# iot_scheme.net
KiCad netlist of a schematic drawn in EAGLE
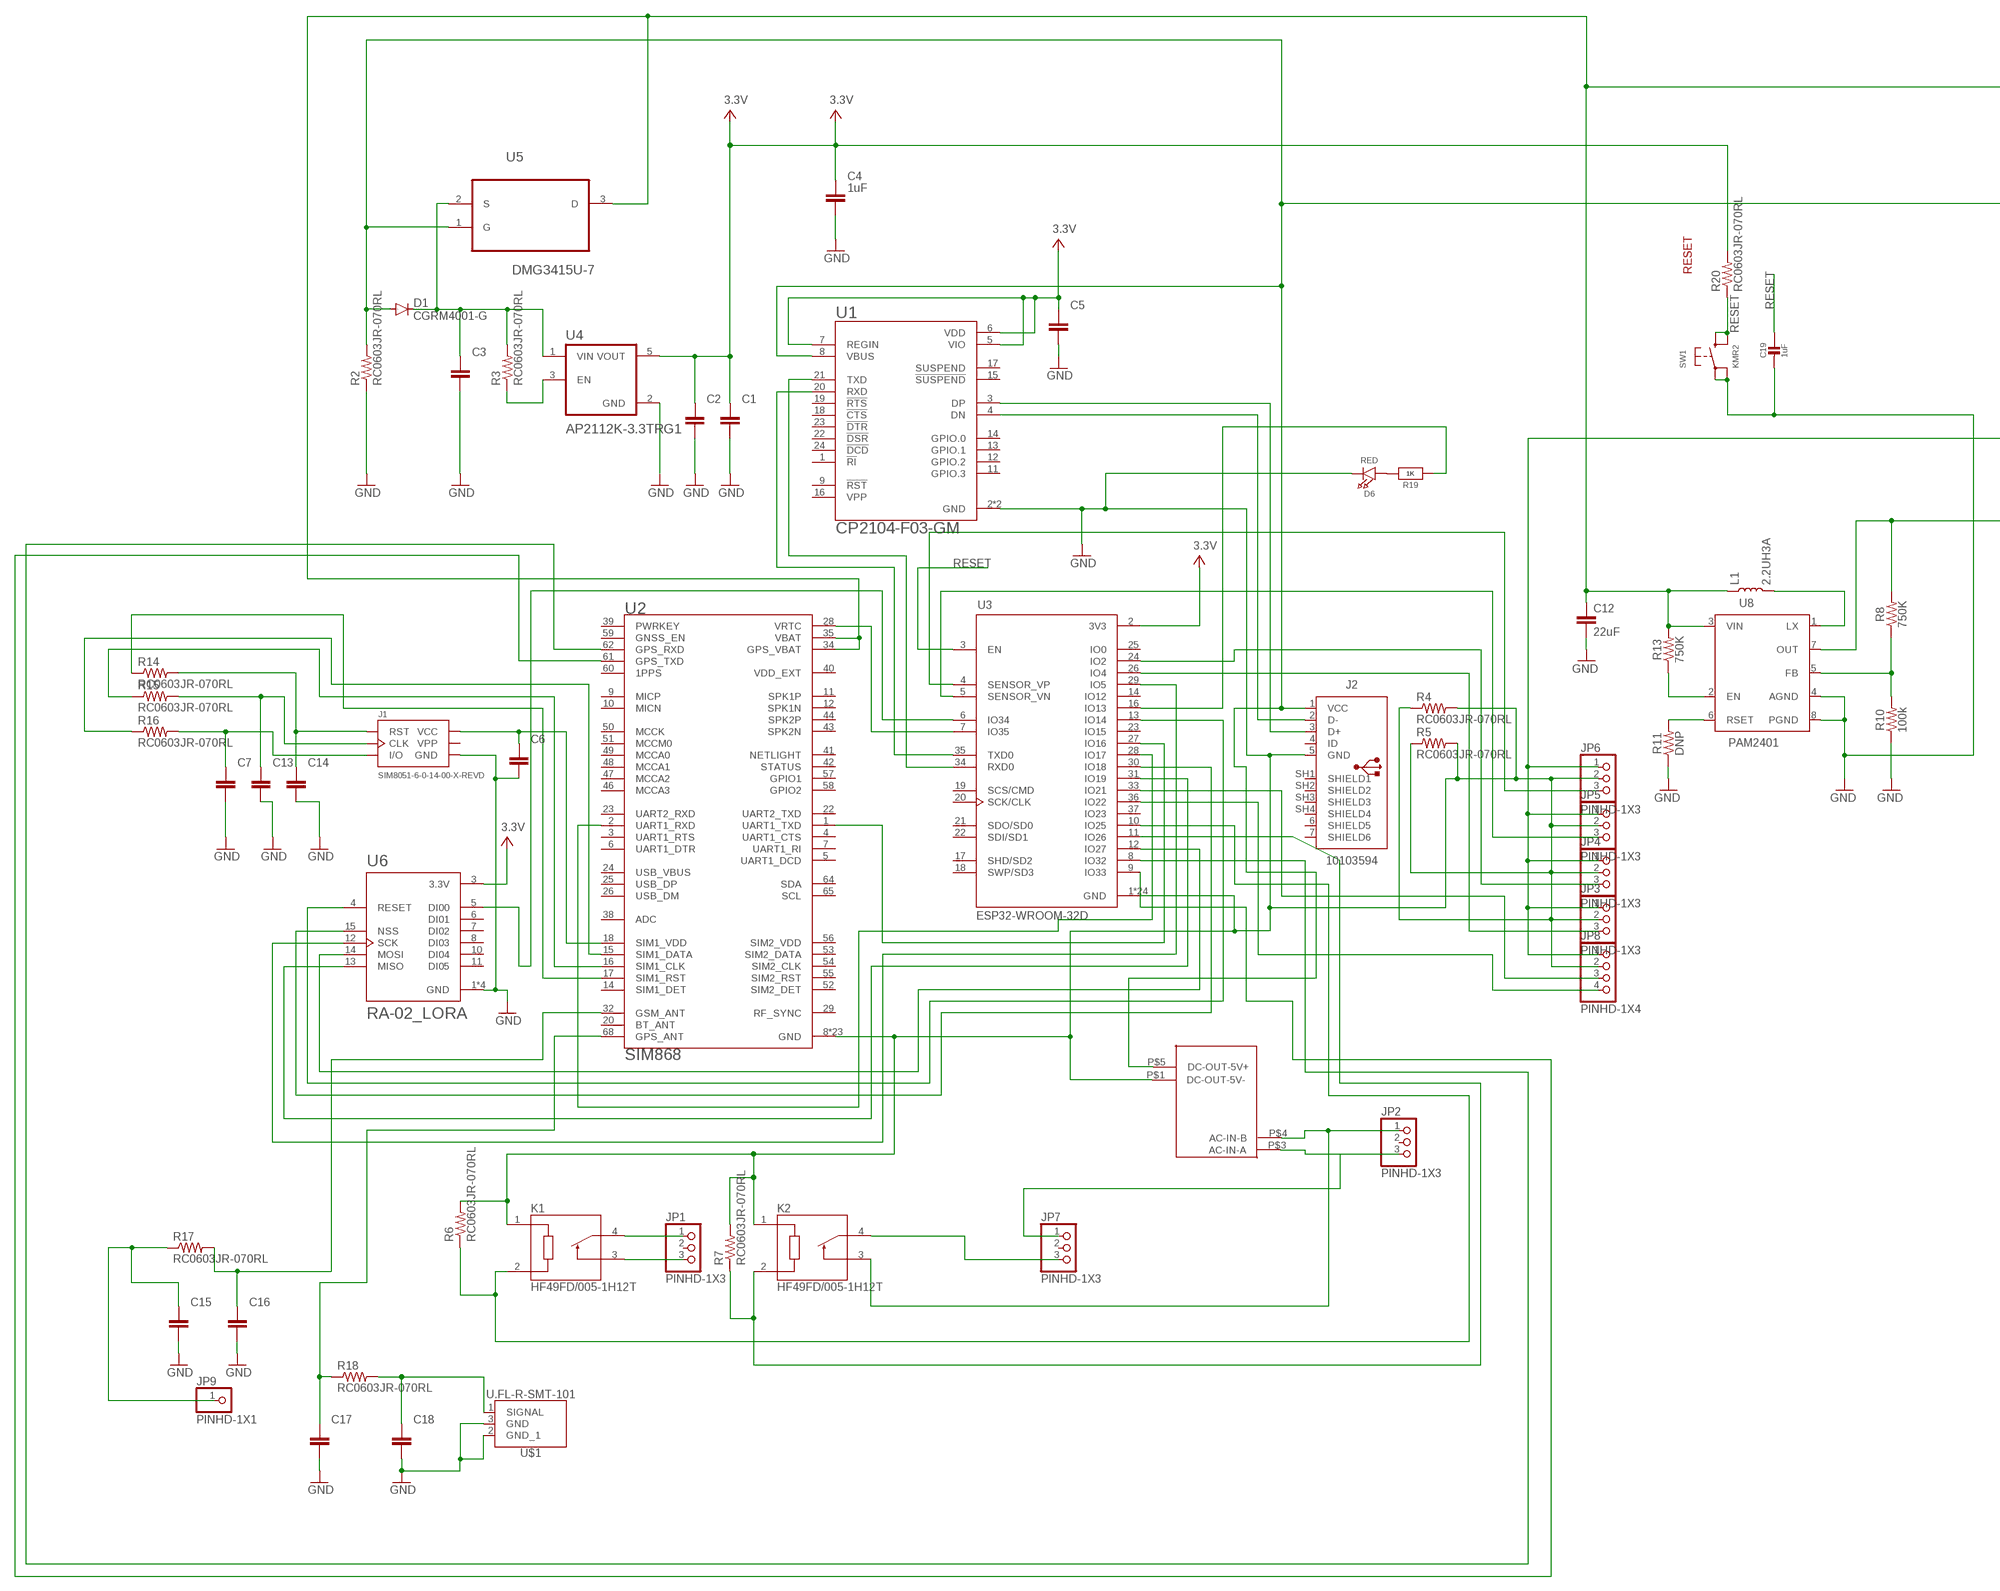
[diagram p0: schematic, sheet 1, part 1 of 2]
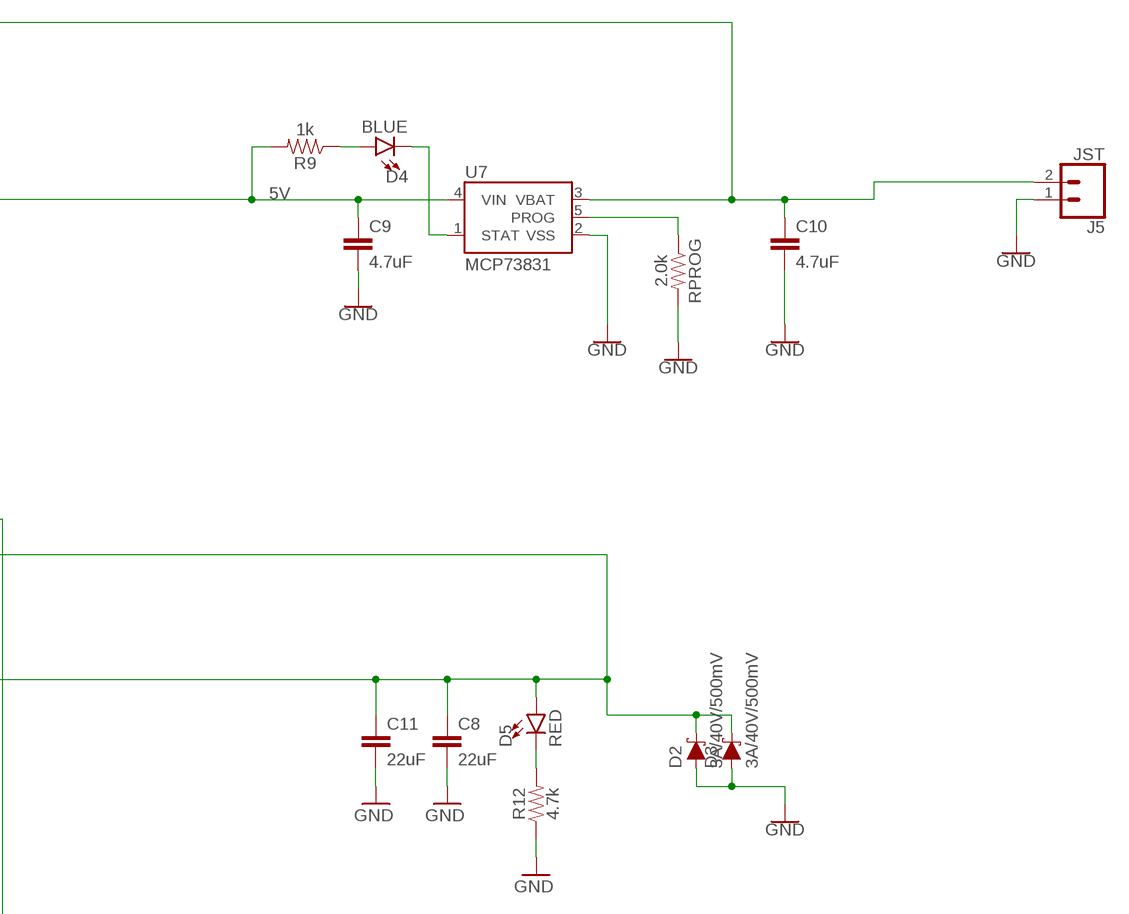
[diagram p1: schematic, sheet 1, part 2 of 2]

(export (version "E")
  (design (tool "Eeschema 10.0.6"))
  (components
    (comp (ref "C1")
      (value "C_CHIP-0603(1608-METRIC)")
      (footprint "eagle-import:CAPC1608X85")
      (libsource (lib "eagle-import") (part "CCHIP-0603(1608-METRIC)_"))
    )
    (comp (ref "C2")
      (value "C_CHIP-0603(1608-METRIC)")
      (footprint "eagle-import:CAPC1608X85")
      (libsource (lib "eagle-import") (part "CCHIP-0603(1608-METRIC)_"))
    )
    (comp (ref "C3")
      (value "C_CHIP-0603(1608-METRIC)")
      (footprint "eagle-import:CAPC1608X85")
      (libsource (lib "eagle-import") (part "CCHIP-0603(1608-METRIC)_"))
    )
    (comp (ref "C4")
      (value "1uF")
      (footprint "eagle-import:CAPC1608X85")
      (libsource (lib "eagle-import") (part "CCHIP-0603(1608-METRIC)_"))
    )
    (comp (ref "C5")
      (value "C_CHIP-0603(1608-METRIC)")
      (footprint "eagle-import:CAPC1608X85")
      (libsource (lib "eagle-import") (part "CCHIP-0603(1608-METRIC)_"))
    )
    (comp (ref "C6")
      (value "C_CHIP-0603(1608-METRIC)")
      (footprint "eagle-import:CAPC1608X85")
      (libsource (lib "eagle-import") (part "CCHIP-0603(1608-METRIC)_"))
    )
    (comp (ref "C7")
      (value "C_CHIP-0603(1608-METRIC)")
      (footprint "eagle-import:CAPC1608X85")
      (libsource (lib "eagle-import") (part "CCHIP-0603(1608-METRIC)_"))
    )
    (comp (ref "C8")
      (value "22uF")
      (footprint "eagle-import:0805")
      (libsource (lib "eagle-import") (part "22UF-0805-6.3V-20%"))
    )
    (comp (ref "C9")
      (value "4.7uF")
      (footprint "eagle-import:0603")
      (libsource (lib "eagle-import") (part "4.7UF0603"))
    )
    (comp (ref "C10")
      (value "4.7uF")
      (footprint "eagle-import:0603")
      (libsource (lib "eagle-import") (part "4.7UF0603"))
    )
    (comp (ref "C11")
      (value "22uF")
      (footprint "eagle-import:0805")
      (libsource (lib "eagle-import") (part "22UF-0805-6.3V-20%"))
    )
    (comp (ref "C12")
      (value "22uF")
      (footprint "eagle-import:0805")
      (libsource (lib "eagle-import") (part "22UF-0805-6.3V-20%"))
    )
    (comp (ref "C13")
      (value "C_CHIP-0603(1608-METRIC)")
      (footprint "eagle-import:CAPC1608X85")
      (libsource (lib "eagle-import") (part "CCHIP-0603(1608-METRIC)_"))
    )
    (comp (ref "C14")
      (value "C_CHIP-0603(1608-METRIC)")
      (footprint "eagle-import:CAPC1608X85")
      (libsource (lib "eagle-import") (part "CCHIP-0603(1608-METRIC)_"))
    )
    (comp (ref "C15")
      (value "C_CHIP-0603(1608-METRIC)")
      (footprint "eagle-import:CAPC1608X85")
      (libsource (lib "eagle-import") (part "CCHIP-0603(1608-METRIC)_"))
    )
    (comp (ref "C16")
      (value "C_CHIP-0603(1608-METRIC)")
      (footprint "eagle-import:CAPC1608X85")
      (libsource (lib "eagle-import") (part "CCHIP-0603(1608-METRIC)_"))
    )
    (comp (ref "C17")
      (value "C_CHIP-0603(1608-METRIC)")
      (footprint "eagle-import:CAPC1608X85")
      (libsource (lib "eagle-import") (part "CCHIP-0603(1608-METRIC)_"))
    )
    (comp (ref "C18")
      (value "C_CHIP-0603(1608-METRIC)")
      (footprint "eagle-import:CAPC1608X85")
      (libsource (lib "eagle-import") (part "CCHIP-0603(1608-METRIC)_"))
    )
    (comp (ref "C19")
      (value "1uF")
      (footprint "eagle-import:0603-NO")
      (libsource (lib "eagle-import") (part "CAP_CERAMIC0603_NO"))
    )
    (comp (ref "D1")
      (value "CGRM4001-G")
      (footprint "eagle-import:SOD-123_MINI-SMA")
      (libsource (lib "eagle-import") (part "CGRM400-G1"))
    )
    (comp (ref "D2")
      (value "3A/40V/500mV")
      (footprint "eagle-import:SMA-DIODE")
      (libsource (lib "eagle-import") (part "DIODE-SCHOTTKY-B340A"))
    )
    (comp (ref "D3")
      (value "3A/40V/500mV")
      (footprint "eagle-import:SMA-DIODE")
      (libsource (lib "eagle-import") (part "DIODE-SCHOTTKY-B340A"))
    )
    (comp (ref "D4")
      (value "BLUE")
      (footprint "eagle-import:LED-0603")
      (libsource (lib "eagle-import") (part "LED-BLUE0603"))
    )
    (comp (ref "D5")
      (value "RED")
      (footprint "eagle-import:LED-0603")
      (libsource (lib "eagle-import") (part "LED-RED0603"))
    )
    (comp (ref "D6")
      (value "RED")
      (footprint "eagle-import:CHIPLED_0805_NOOUTLINE")
      (libsource (lib "eagle-import") (part "LED0805_NOOUTLINE"))
    )
    (comp (ref "J1")
      (value "SIM8051-6-0-14-00-X-REVD")
      (footprint "eagle-import:GCT_SIM8051-6-0-14-00-X-REVD")
      (fields (field (name "MF") "Global Connector Technology") (field (name "MP") "SIM8051-6-0-14-00-A"))
      (libsource (lib "eagle-import") (part "SIM8051-6-0-14-00-X-REVD"))
    )
    (comp (ref "J2")
      (value "10103594")
      (footprint "eagle-import:10103594")
      (fields (field (name "MANUFACTURER") "Amphenol ICC (FCI)") (field (name "MPN") "10103594-0001LF"))
      (libsource (lib "eagle-import") (part "10103594"))
    )
    (comp (ref "J5")
      (value "JST")
      (footprint "eagle-import:JST-2-SMD")
      (libsource (lib "eagle-import") (part "CONN_02-JST-2MM-SMT"))
    )
    (comp (ref "JP1")
      (value "PINHD-1X3")
      (footprint "eagle-import:1X03")
      (libsource (lib "eagle-import") (part "PINHD-1X3"))
    )
    (comp (ref "JP2")
      (value "PINHD-1X3")
      (footprint "eagle-import:1X03")
      (libsource (lib "eagle-import") (part "PINHD-1X3"))
    )
    (comp (ref "JP3")
      (value "PINHD-1X3")
      (footprint "eagle-import:1X03")
      (libsource (lib "eagle-import") (part "PINHD-1X3"))
    )
    (comp (ref "JP4")
      (value "PINHD-1X3")
      (footprint "eagle-import:1X03")
      (libsource (lib "eagle-import") (part "PINHD-1X3"))
    )
    (comp (ref "JP5")
      (value "PINHD-1X3")
      (footprint "eagle-import:1X03")
      (libsource (lib "eagle-import") (part "PINHD-1X3"))
    )
    (comp (ref "JP6")
      (value "PINHD-1X3")
      (footprint "eagle-import:1X03")
      (libsource (lib "eagle-import") (part "PINHD-1X3"))
    )
    (comp (ref "JP7")
      (value "PINHD-1X3")
      (footprint "eagle-import:1X03")
      (libsource (lib "eagle-import") (part "PINHD-1X3"))
    )
    (comp (ref "JP8")
      (value "PINHD-1X4")
      (footprint "eagle-import:1X04")
      (libsource (lib "eagle-import") (part "PINHD-1X4"))
    )
    (comp (ref "JP9")
      (value "PINHD-1X1")
      (footprint "eagle-import:1X01")
      (libsource (lib "eagle-import") (part "PINHD-1X1"))
    )
    (comp (ref "K1")
      (value "HF49FD/005-1H12T")
      (footprint "eagle-import:RELAY_HF49FD_005-1H12T")
      (fields (field (name "MF") "Hongfa"))
      (libsource (lib "eagle-import") (part "HF49FD/005-1H12T"))
    )
    (comp (ref "K2")
      (value "HF49FD/005-1H12T")
      (footprint "eagle-import:RELAY_HF49FD_005-1H12T")
      (fields (field (name "MF") "Hongfa"))
      (libsource (lib "eagle-import") (part "HF49FD/005-1H12T"))
    )
    (comp (ref "L1")
      (value "2.2UH3A")
      (footprint "eagle-import:INDUCTOR_4X4MM")
      (libsource (lib "eagle-import") (part "INDUCTOR-IFSC1515AHER2R2M01"))
    )
    (comp (ref "R1")
      (value "AC-DC-5V")
      (footprint "eagle-import:MYFOOT")
      (libsource (lib "eagle-import") (part "AC-DC-5V"))
    )
    (comp (ref "R2")
      (value "RC0603JR-070RL")
      (footprint "eagle-import:RES_0603")
      (fields
        (field (name "DIGIKEY_PART_NUMBER") "311-0.0GRTR-ND")
        (field (name "MANUFACTURER") "Yageo")
        (field (name "CREATED_BY") "PCBLayout.com")
      )
      (libsource (lib "eagle-import") (part "RC0603JR-070RL"))
    )
    (comp (ref "R3")
      (value "RC0603JR-070RL")
      (footprint "eagle-import:RES_0603")
      (fields
        (field (name "DIGIKEY_PART_NUMBER") "311-0.0GRTR-ND")
        (field (name "MANUFACTURER") "Yageo")
        (field (name "CREATED_BY") "PCBLayout.com")
      )
      (libsource (lib "eagle-import") (part "RC0603JR-070RL"))
    )
    (comp (ref "R4")
      (value "RC0603JR-070RL")
      (footprint "eagle-import:RES_0603")
      (fields
        (field (name "DIGIKEY_PART_NUMBER") "311-0.0GRTR-ND")
        (field (name "MANUFACTURER") "Yageo")
        (field (name "CREATED_BY") "PCBLayout.com")
      )
      (libsource (lib "eagle-import") (part "RC0603JR-070RL"))
    )
    (comp (ref "R5")
      (value "RC0603JR-070RL")
      (footprint "eagle-import:RES_0603")
      (fields
        (field (name "DIGIKEY_PART_NUMBER") "311-0.0GRTR-ND")
        (field (name "MANUFACTURER") "Yageo")
        (field (name "CREATED_BY") "PCBLayout.com")
      )
      (libsource (lib "eagle-import") (part "RC0603JR-070RL"))
    )
    (comp (ref "R6")
      (value "RC0603JR-070RL")
      (footprint "eagle-import:RES_0603")
      (fields
        (field (name "DIGIKEY_PART_NUMBER") "311-0.0GRTR-ND")
        (field (name "MANUFACTURER") "Yageo")
        (field (name "CREATED_BY") "PCBLayout.com")
      )
      (libsource (lib "eagle-import") (part "RC0603JR-070RL"))
    )
    (comp (ref "R7")
      (value "RC0603JR-070RL")
      (footprint "eagle-import:RES_0603")
      (fields
        (field (name "DIGIKEY_PART_NUMBER") "311-0.0GRTR-ND")
        (field (name "MANUFACTURER") "Yageo")
        (field (name "CREATED_BY") "PCBLayout.com")
      )
      (libsource (lib "eagle-import") (part "RC0603JR-070RL"))
    )
    (comp (ref "R8")
      (value "750K")
      (footprint "eagle-import:0603")
      (libsource (lib "eagle-import") (part "750KOHM-0603-1/10W-1%"))
    )
    (comp (ref "R9")
      (value "1k")
      (footprint "eagle-import:0603")
      (libsource (lib "eagle-import") (part "1KOHM-0603-1/10W-1%"))
    )
    (comp (ref "R10")
      (value "100k")
      (footprint "eagle-import:0603")
      (libsource (lib "eagle-import") (part "100KOHM-0603-1/10W-1%"))
    )
    (comp (ref "R11")
      (value "DNP")
      (footprint "eagle-import:0603")
      (libsource (lib "eagle-import") (part "100KOHM-0603-1/10W-1%"))
    )
    (comp (ref "R12")
      (value "4.7k")
      (footprint "eagle-import:0603")
      (libsource (lib "eagle-import") (part "4.7KOHM-0603-1/10W-1%"))
    )
    (comp (ref "R13")
      (value "750K")
      (footprint "eagle-import:0603")
      (libsource (lib "eagle-import") (part "750KOHM-0603-1/10W-1%"))
    )
    (comp (ref "R14")
      (value "RC0603JR-070RL")
      (footprint "eagle-import:RES_0603")
      (fields
        (field (name "DIGIKEY_PART_NUMBER") "311-0.0GRTR-ND")
        (field (name "MANUFACTURER") "Yageo")
        (field (name "CREATED_BY") "PCBLayout.com")
      )
      (libsource (lib "eagle-import") (part "RC0603JR-070RL"))
    )
    (comp (ref "R15")
      (value "RC0603JR-070RL")
      (footprint "eagle-import:RES_0603")
      (fields
        (field (name "DIGIKEY_PART_NUMBER") "311-0.0GRTR-ND")
        (field (name "MANUFACTURER") "Yageo")
        (field (name "CREATED_BY") "PCBLayout.com")
      )
      (libsource (lib "eagle-import") (part "RC0603JR-070RL"))
    )
    (comp (ref "R16")
      (value "RC0603JR-070RL")
      (footprint "eagle-import:RES_0603")
      (fields
        (field (name "DIGIKEY_PART_NUMBER") "311-0.0GRTR-ND")
        (field (name "MANUFACTURER") "Yageo")
        (field (name "CREATED_BY") "PCBLayout.com")
      )
      (libsource (lib "eagle-import") (part "RC0603JR-070RL"))
    )
    (comp (ref "R17")
      (value "RC0603JR-070RL")
      (footprint "eagle-import:RES_0603")
      (fields
        (field (name "DIGIKEY_PART_NUMBER") "311-0.0GRTR-ND")
        (field (name "MANUFACTURER") "Yageo")
        (field (name "CREATED_BY") "PCBLayout.com")
      )
      (libsource (lib "eagle-import") (part "RC0603JR-070RL"))
    )
    (comp (ref "R18")
      (value "RC0603JR-070RL")
      (footprint "eagle-import:RES_0603")
      (fields
        (field (name "DIGIKEY_PART_NUMBER") "311-0.0GRTR-ND")
        (field (name "MANUFACTURER") "Yageo")
        (field (name "CREATED_BY") "PCBLayout.com")
      )
      (libsource (lib "eagle-import") (part "RC0603JR-070RL"))
    )
    (comp (ref "R19")
      (value "1K")
      (footprint "eagle-import:0603-NO")
      (libsource (lib "eagle-import") (part "RESISTOR_0603_NOOUT"))
    )
    (comp (ref "R20")
      (value "RC0603JR-070RL")
      (footprint "eagle-import:RES_0603")
      (fields
        (field (name "DIGIKEY_PART_NUMBER") "311-0.0GRTR-ND")
        (field (name "MANUFACTURER") "Yageo")
        (field (name "CREATED_BY") "PCBLayout.com")
      )
      (libsource (lib "eagle-import") (part "RC0603JR-070RL"))
    )
    (comp (ref "RPROG")
      (value "2.0k")
      (footprint "eagle-import:0603")
      (libsource (lib "eagle-import") (part "2.0KOHM-0603-1/10W-5%"))
    )
    (comp (ref "SW1")
      (value "KMR2")
      (footprint "eagle-import:BTN_KMR2_4.6X2.8")
      (libsource (lib "eagle-import") (part "SWITCH_TACT_SMT4.6X2.8"))
    )
    (comp (ref "U$1")
      (value "U.FL-R-SMT-101")
      (footprint "eagle-import:U.FL-R-SMT-1(XX)")
      (fields
        (field (name "MANUFACTURER") " Hirose Electric Co Ltd")
        (field (name "MPN") "U.FL-R-SMT-1(01) ")
      )
      (libsource (lib "eagle-import") (part "U.FL-R-SMT-101"))
    )
    (comp (ref "U1")
      (value "CP2104-F03-GM")
      (footprint "eagle-import:QFN50P400X400X80-25N")
      (fields (field (name "MF") "Silicon Labs") (field (name "MP") "CP2104"))
      (libsource (lib "eagle-import") (part "CP2104-F03-GM"))
    )
    (comp (ref "U2")
      (value "SIM868")
      (footprint "eagle-import:XCVR_SIM868")
      (fields (field (name "MF") "MikroElektronika"))
      (libsource (lib "eagle-import") (part "SIM868"))
    )
    (comp (ref "U3")
      (value "ESP32-WROOM-32D")
      (footprint "eagle-import:MODULE_ESP32-WROOM-32D")
      (fields (field (name "MF") "Espressif Systems"))
      (libsource (lib "eagle-import") (part "ESP32-WROOM-32D"))
    )
    (comp (ref "U4")
      (value "AP2112K-3.3TRG1")
      (footprint "eagle-import:SOT95P285X140-5N")
      (fields (field (name "MF") "Diodes Zetex"))
      (libsource (lib "eagle-import") (part "AP2112K-3.3TRG1"))
    )
    (comp (ref "U5")
      (value "DMG3415U-7")
      (footprint "eagle-import:SOT95P240X105-3N")
      (fields (field (name "MF") "Diodes Inc."))
      (libsource (lib "eagle-import") (part "DMG3415U-7"))
    )
    (comp (ref "U6")
      (value "RA-02_LORA")
      (footprint "eagle-import:MODULE_RA-02_LORA")
      (fields (field (name "MF") "AI-Thinker") (field (name "MP") "Ra-02 LoRa"))
      (libsource (lib "eagle-import") (part "RA-02_LORA"))
    )
    (comp (ref "U7")
      (value "MCP73831")
      (footprint "eagle-import:SOT23-5")
      (libsource (lib "eagle-import") (part "MCP73831"))
    )
    (comp (ref "U8")
      (value "PAM2401")
      (footprint "eagle-import:MSOP8")
      (libsource (lib "eagle-import") (part "PAM2401"))
    )
  )
  (nets
    (net (code "1") (name "/5V") (class "Default")
      (node (ref "C9") (pin "1") (pinfunction "1_1") (pintype "passive"))
      (node (ref "D1") (pin "A") (pinfunction "A_A") (pintype "passive"))
      (node (ref "J2") (pin "1") (pinfunction "VCC_1") (pintype "power_in"))
      (node (ref "R1") (pin "P$5") (pinfunction "DC-OUT-5V+_P$5") (pintype "bidirectional"))
      (node (ref "R2") (pin "2") (pinfunction "2_2") (pintype "passive"))
      (node (ref "R9") (pin "2") (pinfunction "2_2") (pintype "passive"))
      (node (ref "U1") (pin "8") (pinfunction "VBUS_8") (pintype "input"))
      (node (ref "U5") (pin "1") (pinfunction "G_1") (pintype "power_in"))
      (node (ref "U7") (pin "4") (pinfunction "VIN_4") (pintype "power_in"))
    )
    (net (code "2") (name "/RESET") (class "Default")
      (node (ref "C19") (pin "1") (pinfunction "1_1") (pintype "passive"))
      (node (ref "R20") (pin "1") (pinfunction "1_1") (pintype "passive"))
      (node (ref "SW1") (pin "B") (pinfunction "S_B") (pintype "passive"))
      (node (ref "SW1") (pin "B'") (pinfunction "S1_B'") (pintype "passive"))
      (node (ref "U3") (pin "3") (pinfunction "EN_3") (pintype "input"))
    )
    (net (code "3") (name "/SHIELD1") (class "Default")
      (node (ref "J2") (pin "SH1") (pinfunction "SHIELD1_SH1") (pintype "power_in"))
    )
    (net (code "4") (name "/SHIELD2") (class "Default")
      (node (ref "J2") (pin "SH2") (pinfunction "SHIELD2_SH2") (pintype "power_in"))
    )
    (net (code "5") (name "/SHIELD3") (class "Default")
      (node (ref "J2") (pin "SH3") (pinfunction "SHIELD3_SH3") (pintype "power_in"))
    )
    (net (code "6") (name "/SHIELD4") (class "Default")
      (node (ref "J2") (pin "SH4") (pinfunction "SHIELD4_SH4") (pintype "power_in"))
    )
    (net (code "7") (name "/SHIELD5") (class "Default")
      (node (ref "J2") (pin "6") (pinfunction "SHIELD5_6") (pintype "power_in"))
    )
    (net (code "8") (name "/SHIELD6") (class "Default")
      (node (ref "J2") (pin "7") (pinfunction "SHIELD6_7") (pintype "power_in"))
    )
    (net (code "9") (name "/VPP") (class "Default")
      (node (ref "J1") (pin "C6") (pinfunction "VPP_C6") (pintype "power_in"))
    )
    (net (code "10") (name "3.3V") (class "Default")
      (node (ref "C1") (pin "1") (pinfunction "1_1") (pintype "passive"))
      (node (ref "C2") (pin "1") (pinfunction "1_1") (pintype "passive"))
      (node (ref "C4") (pin "1") (pinfunction "1_1") (pintype "passive"))
      (node (ref "C5") (pin "1") (pinfunction "1_1") (pintype "passive"))
      (node (ref "R20") (pin "2") (pinfunction "2_2") (pintype "passive"))
      (node (ref "U1") (pin "5") (pinfunction "VIO_5") (pintype "power_in"))
      (node (ref "U1") (pin "6") (pinfunction "VDD_6") (pintype "power_in"))
      (node (ref "U1") (pin "7") (pinfunction "REGIN_7") (pintype "input"))
      (node (ref "U3") (pin "2") (pinfunction "3V3_2") (pintype "power_in"))
      (node (ref "U4") (pin "5") (pinfunction "VOUT_5") (pintype "power_in"))
      (node (ref "U6") (pin "3") (pinfunction "3.3V_3") (pintype "power_in"))
    )
    (net (code "11") (name "GND") (class "Default")
      (node (ref "C1") (pin "2") (pinfunction "2_2") (pintype "passive"))
      (node (ref "C10") (pin "2") (pinfunction "2_2") (pintype "passive"))
      (node (ref "C11") (pin "2") (pinfunction "2_2") (pintype "passive"))
      (node (ref "C12") (pin "2") (pinfunction "2_2") (pintype "passive"))
      (node (ref "C13") (pin "2") (pinfunction "2_2") (pintype "passive"))
      (node (ref "C14") (pin "2") (pinfunction "2_2") (pintype "passive"))
      (node (ref "C15") (pin "2") (pinfunction "2_2") (pintype "passive"))
      (node (ref "C16") (pin "2") (pinfunction "2_2") (pintype "passive"))
      (node (ref "C17") (pin "2") (pinfunction "2_2") (pintype "passive"))
      (node (ref "C18") (pin "2") (pinfunction "2_2") (pintype "passive"))
      (node (ref "C19") (pin "2") (pinfunction "2_2") (pintype "passive"))
      (node (ref "C2") (pin "2") (pinfunction "2_2") (pintype "passive"))
      (node (ref "C3") (pin "2") (pinfunction "2_2") (pintype "passive"))
      (node (ref "C4") (pin "2") (pinfunction "2_2") (pintype "passive"))
      (node (ref "C5") (pin "2") (pinfunction "2_2") (pintype "passive"))
      (node (ref "C6") (pin "2") (pinfunction "2_2") (pintype "passive"))
      (node (ref "C7") (pin "2") (pinfunction "2_2") (pintype "passive"))
      (node (ref "C8") (pin "2") (pinfunction "2_2") (pintype "passive"))
      (node (ref "C9") (pin "2") (pinfunction "2_2") (pintype "passive"))
      (node (ref "D2") (pin "A") (pinfunction "A_A") (pintype "passive"))
      (node (ref "D3") (pin "A") (pinfunction "A_A") (pintype "passive"))
      (node (ref "D6") (pin "C") (pinfunction "C_C") (pintype "passive"))
      (node (ref "J1") (pin "C5") (pinfunction "GND_C5") (pintype "power_in"))
      (node (ref "J2") (pin "5") (pinfunction "GND_5") (pintype "power_in"))
      (node (ref "J5") (pin "1") (pinfunction "2_1") (pintype "passive"))
      (node (ref "JP3") (pin "2") (pinfunction "2_2") (pintype "passive"))
      (node (ref "JP4") (pin "2") (pinfunction "2_2") (pintype "passive"))
      (node (ref "JP5") (pin "2") (pinfunction "2_2") (pintype "passive"))
      (node (ref "JP6") (pin "2") (pinfunction "2_2") (pintype "passive"))
      (node (ref "JP8") (pin "2") (pinfunction "2_2") (pintype "passive"))
      (node (ref "K1") (pin "1") (pinfunction "L1_1") (pintype "passive"))
      (node (ref "K2") (pin "1") (pinfunction "L1_1") (pintype "passive"))
      (node (ref "R1") (pin "P$1") (pinfunction "DC-OUT-5V-_P$1") (pintype "bidirectional"))
      (node (ref "R10") (pin "1") (pinfunction "1_1") (pintype "passive"))
      (node (ref "R11") (pin "1") (pinfunction "1_1") (pintype "passive"))
      (node (ref "R12") (pin "1") (pinfunction "1_1") (pintype "passive"))
      (node (ref "R2") (pin "1") (pinfunction "1_1") (pintype "passive"))
      (node (ref "R4") (pin "1") (pinfunction "1_1") (pintype "passive"))
      (node (ref "R4") (pin "2") (pinfunction "2_2") (pintype "passive"))
      (node (ref "R5") (pin "1") (pinfunction "1_1") (pintype "passive"))
      (node (ref "R5") (pin "2") (pinfunction "2_2") (pintype "passive"))
      (node (ref "R6") (pin "2") (pinfunction "2_2") (pintype "passive"))
      (node (ref "R7") (pin "2") (pinfunction "2_2") (pintype "passive"))
      (node (ref "RPROG") (pin "2") (pinfunction "2_2") (pintype "passive"))
      (node (ref "SW1") (pin "A") (pinfunction "P_A") (pintype "passive"))
      (node (ref "SW1") (pin "A'") (pinfunction "P1_A'") (pintype "passive"))
      (node (ref "U$1") (pin "2") (pinfunction "GND_1_2") (pintype "bidirectional"))
      (node (ref "U$1") (pin "3") (pinfunction "GND_3") (pintype "bidirectional"))
      (node (ref "U1") (pin "2") (pinfunction "GND_2") (pintype "power_in"))
      (node (ref "U1") (pin "25") (pinfunction "GND_25") (pintype "power_in"))
      (node (ref "U2") (pin "13") (pinfunction "GND_13") (pintype "power_in"))
      (node (ref "U2") (pin "19") (pinfunction "GND_19") (pintype "power_in"))
      (node (ref "U2") (pin "21") (pinfunction "GND_21") (pintype "power_in"))
      (node (ref "U2") (pin "27") (pinfunction "GND_27") (pintype "power_in"))
      (node (ref "U2") (pin "30") (pinfunction "GND_30") (pintype "power_in"))
      (node (ref "U2") (pin "31") (pinfunction "GND_31") (pintype "power_in"))
      (node (ref "U2") (pin "33") (pinfunction "GND_33") (pintype "power_in"))
      (node (ref "U2") (pin "36") (pinfunction "GND_36") (pintype "power_in"))
      (node (ref "U2") (pin "37") (pinfunction "GND_37") (pintype "power_in"))
      (node (ref "U2") (pin "45") (pinfunction "GND_45") (pintype "power_in"))
      (node (ref "U2") (pin "63") (pinfunction "GND_63") (pintype "power_in"))
      (node (ref "U2") (pin "66") (pinfunction "GND_66") (pintype "power_in"))
      (node (ref "U2") (pin "67") (pinfunction "GND_67") (pintype "power_in"))
      (node (ref "U2") (pin "69") (pinfunction "GND_69") (pintype "power_in"))
      (node (ref "U2") (pin "70") (pinfunction "GND_70") (pintype "power_in"))
      (node (ref "U2") (pin "71") (pinfunction "GND_71") (pintype "power_in"))
      (node (ref "U2") (pin "72") (pinfunction "GND_72") (pintype "power_in"))
      (node (ref "U2") (pin "73") (pinfunction "GND_73") (pintype "power_in"))
      (node (ref "U2") (pin "74") (pinfunction "GND_74") (pintype "power_in"))
      (node (ref "U2") (pin "75") (pinfunction "GND_75") (pintype "power_in"))
      (node (ref "U2") (pin "76") (pinfunction "GND_76") (pintype "power_in"))
      (node (ref "U2") (pin "77") (pinfunction "GND_77") (pintype "power_in"))
      (node (ref "U2") (pin "8") (pinfunction "GND_8") (pintype "power_in"))
      (node (ref "U3") (pin "1") (pinfunction "GND_1") (pintype "power_in"))
      (node (ref "U3") (pin "15") (pinfunction "GND_15") (pintype "power_in"))
      (node (ref "U3") (pin "38") (pinfunction "GND_38") (pintype "power_in"))
      (node (ref "U3") (pin "39_1") (pinfunction "GND_39_1") (pintype "power_in"))
      (node (ref "U3") (pin "39_10") (pinfunction "GND_39_10") (pintype "power_in"))
      (node (ref "U3") (pin "39_11") (pinfunction "GND_39_11") (pintype "power_in"))
      (node (ref "U3") (pin "39_12") (pinfunction "GND_39_12") (pintype "power_in"))
      (node (ref "U3") (pin "39_13") (pinfunction "GND_39_13") (pintype "power_in"))
      (node (ref "U3") (pin "39_14") (pinfunction "GND_39_14") (pintype "power_in"))
      (node (ref "U3") (pin "39_15") (pinfunction "GND_39_15") (pintype "power_in"))
      (node (ref "U3") (pin "39_16") (pinfunction "GND_39_16") (pintype "power_in"))
      (node (ref "U3") (pin "39_17") (pinfunction "GND_39_17") (pintype "power_in"))
      (node (ref "U3") (pin "39_18") (pinfunction "GND_39_18") (pintype "power_in"))
      (node (ref "U3") (pin "39_19") (pinfunction "GND_39_19") (pintype "power_in"))
      (node (ref "U3") (pin "39_2") (pinfunction "GND_39_2") (pintype "power_in"))
      (node (ref "U3") (pin "39_20") (pinfunction "GND_39_20") (pintype "power_in"))
      (node (ref "U3") (pin "39_21") (pinfunction "GND_39_21") (pintype "power_in"))
      (node (ref "U3") (pin "39_3") (pinfunction "GND_39_3") (pintype "power_in"))
      (node (ref "U3") (pin "39_4") (pinfunction "GND_39_4") (pintype "power_in"))
      (node (ref "U3") (pin "39_5") (pinfunction "GND_39_5") (pintype "power_in"))
      (node (ref "U3") (pin "39_6") (pinfunction "GND_39_6") (pintype "power_in"))
      (node (ref "U3") (pin "39_7") (pinfunction "GND_39_7") (pintype "power_in"))
      (node (ref "U3") (pin "39_8") (pinfunction "GND_39_8") (pintype "power_in"))
      (node (ref "U3") (pin "39_9") (pinfunction "GND_39_9") (pintype "power_in"))
      (node (ref "U4") (pin "2") (pinfunction "GND_2") (pintype "power_in"))
      (node (ref "U6") (pin "1") (pinfunction "GND_1") (pintype "power_in"))
      (node (ref "U6") (pin "16") (pinfunction "GND_16") (pintype "power_in"))
      (node (ref "U6") (pin "2") (pinfunction "GND_2") (pintype "power_in"))
      (node (ref "U6") (pin "9") (pinfunction "GND_9") (pintype "power_in"))
      (node (ref "U7") (pin "2") (pinfunction "VSS_2") (pintype "power_in"))
      (node (ref "U8") (pin "4") (pinfunction "AGND_4") (pintype "bidirectional"))
      (node (ref "U8") (pin "8") (pinfunction "PGND_8") (pintype "bidirectional"))
    )
    (net (code "12") (name "Net-(C15-Pad1)") (class "Default")
      (node (ref "C15") (pin "1") (pinfunction "1_1") (pintype "passive"))
      (node (ref "JP9") (pin "1") (pinfunction "1_1") (pintype "passive"))
      (node (ref "R17") (pin "1") (pinfunction "1_1") (pintype "passive"))
    )
    (net (code "13") (name "Net-(D4-PadA)") (class "Default")
      (node (ref "D4") (pin "A") (pinfunction "A_A") (pintype "passive"))
      (node (ref "R9") (pin "1") (pinfunction "1_1") (pintype "passive"))
    )
    (net (code "14") (name "Net-(D5-PadC)") (class "Default")
      (node (ref "D5") (pin "C") (pinfunction "C_C") (pintype "passive"))
      (node (ref "R12") (pin "2") (pinfunction "2_2") (pintype "passive"))
    )
    (net (code "15") (name "Net-(D6-PadA)") (class "Default")
      (node (ref "D6") (pin "A") (pinfunction "A_A") (pintype "passive"))
      (node (ref "R19") (pin "2") (pinfunction "2_2") (pintype "passive"))
    )
    (net (code "16") (name "Net-(J1-CLK)") (class "Default")
      (node (ref "C13") (pin "1") (pinfunction "1_1") (pintype "passive"))
      (node (ref "J1") (pin "C3") (pinfunction "CLK_C3") (pintype "input"))
      (node (ref "R15") (pin "2") (pinfunction "2_2") (pintype "passive"))
    )
    (net (code "17") (name "Net-(J1-I{slash}O)") (class "Default")
      (node (ref "C7") (pin "1") (pinfunction "1_1") (pintype "passive"))
      (node (ref "J1") (pin "C7") (pinfunction "I/O_C7") (pintype "bidirectional"))
      (node (ref "R16") (pin "2") (pinfunction "2_2") (pintype "passive"))
    )
    (net (code "18") (name "Net-(J1-RST)") (class "Default")
      (node (ref "C14") (pin "1") (pinfunction "1_1") (pintype "passive"))
      (node (ref "J1") (pin "C2") (pinfunction "RST_C2") (pintype "input"))
      (node (ref "R14") (pin "2") (pinfunction "2_2") (pintype "passive"))
    )
    (net (code "19") (name "Net-(J1-VCC)") (class "Default")
      (node (ref "C6") (pin "1") (pinfunction "1_1") (pintype "passive"))
      (node (ref "J1") (pin "C1") (pinfunction "VCC_C1") (pintype "power_in"))
      (node (ref "U2") (pin "18") (pinfunction "SIM1_VDD_18") (pintype "output"))
    )
    (net (code "20") (name "Net-(J2-D+)") (class "Default")
      (node (ref "J2") (pin "3") (pinfunction "D+_3") (pintype "bidirectional"))
      (node (ref "U1") (pin "3") (pinfunction "DP_3") (pintype "bidirectional"))
    )
    (net (code "21") (name "Net-(J2-D-)") (class "Default")
      (node (ref "J2") (pin "2") (pinfunction "D-_2") (pintype "bidirectional"))
      (node (ref "U1") (pin "4") (pinfunction "DN_4") (pintype "bidirectional"))
    )
    (net (code "22") (name "Net-(J5-1)") (class "Default")
      (node (ref "C10") (pin "1") (pinfunction "1_1") (pintype "passive"))
      (node (ref "C12") (pin "1") (pinfunction "1_1") (pintype "passive"))
      (node (ref "J5") (pin "2") (pinfunction "1_2") (pintype "passive"))
      (node (ref "L1") (pin "P$1") (pinfunction "1_P$1") (pintype "passive"))
      (node (ref "R13") (pin "2") (pinfunction "2_2") (pintype "passive"))
      (node (ref "U2") (pin "34") (pinfunction "GPS_VBAT_34") (pintype "power_in"))
      (node (ref "U2") (pin "35") (pinfunction "VBAT_35") (pintype "power_in"))
      (node (ref "U5") (pin "3") (pinfunction "D_3") (pintype "output"))
      (node (ref "U7") (pin "3") (pinfunction "VBAT_3") (pintype "power_in"))
      (node (ref "U8") (pin "3") (pinfunction "VIN_3") (pintype "bidirectional"))
    )
    (net (code "23") (name "Net-(K1-C1)") (class "Default")
      (node (ref "JP1") (pin "1") (pinfunction "1_1") (pintype "passive"))
      (node (ref "K1") (pin "4") (pinfunction "C1_4") (pintype "passive"))
    )
    (net (code "24") (name "Net-(K1-C2)") (class "Default")
      (node (ref "JP1") (pin "3") (pinfunction "3_3") (pintype "passive"))
      (node (ref "K1") (pin "3") (pinfunction "C2_3") (pintype "passive"))
    )
    (net (code "25") (name "Net-(K1-L2)") (class "Default")
      (node (ref "K1") (pin "2") (pinfunction "L2_2") (pintype "passive"))
      (node (ref "R6") (pin "1") (pinfunction "1_1") (pintype "passive"))
      (node (ref "U3") (pin "10") (pinfunction "IO25_10") (pintype "bidirectional"))
    )
    (net (code "26") (name "Net-(K2-C1)") (class "Default")
      (node (ref "JP7") (pin "3") (pinfunction "3_3") (pintype "passive"))
      (node (ref "K2") (pin "4") (pinfunction "C1_4") (pintype "passive"))
    )
    (net (code "27") (name "Net-(K2-C2)") (class "Default")
      (node (ref "JP2") (pin "1") (pinfunction "1_1") (pintype "passive"))
      (node (ref "K2") (pin "3") (pinfunction "C2_3") (pintype "passive"))
      (node (ref "R1") (pin "P$4") (pinfunction "AC-IN-B_P$4") (pintype "bidirectional"))
    )
    (net (code "28") (name "Net-(K2-L2)") (class "Default")
      (node (ref "K2") (pin "2") (pinfunction "L2_2") (pintype "passive"))
      (node (ref "R7") (pin "1") (pinfunction "1_1") (pintype "passive"))
      (node (ref "U3") (pin "11") (pinfunction "IO26_11") (pintype "bidirectional"))
    )
    (net (code "29") (name "Net-(L1-2)") (class "Default")
      (node (ref "L1") (pin "P$2") (pinfunction "2_P$2") (pintype "passive"))
      (node (ref "U8") (pin "1") (pinfunction "LX_1") (pintype "bidirectional"))
    )
    (net (code "30") (name "Net-(R1-AC-IN-A)") (class "Default")
      (node (ref "JP2") (pin "3") (pinfunction "3_3") (pintype "passive"))
      (node (ref "JP7") (pin "1") (pinfunction "1_1") (pintype "passive"))
      (node (ref "R1") (pin "P$3") (pinfunction "AC-IN-A_P$3") (pintype "bidirectional"))
    )
    (net (code "31") (name "Net-(U$1-SIGNAL)") (class "Default")
      (node (ref "C18") (pin "1") (pinfunction "1_1") (pintype "passive"))
      (node (ref "R18") (pin "2") (pinfunction "2_2") (pintype "passive"))
      (node (ref "U$1") (pin "1") (pinfunction "SIGNAL_1") (pintype "bidirectional"))
    )
    (net (code "32") (name "Net-(U1-RXD)") (class "Default")
      (node (ref "U1") (pin "20") (pinfunction "RXD_20") (pintype "input"))
      (node (ref "U3") (pin "35") (pinfunction "TXD0_35") (pintype "bidirectional"))
    )
    (net (code "33") (name "Net-(U1-TXD)") (class "Default")
      (node (ref "U1") (pin "21") (pinfunction "TXD_21") (pintype "output"))
      (node (ref "U3") (pin "34") (pinfunction "RXD0_34") (pintype "bidirectional"))
    )
    (net (code "34") (name "Net-(U2-GPS_ANT)") (class "Default")
      (node (ref "C17") (pin "1") (pinfunction "1_1") (pintype "passive"))
      (node (ref "R18") (pin "1") (pinfunction "1_1") (pintype "passive"))
      (node (ref "U2") (pin "68") (pinfunction "GPS_ANT_68") (pintype "input"))
    )
    (net (code "35") (name "Net-(U2-GPS_RXD)") (class "Default")
      (node (ref "U2") (pin "62") (pinfunction "GPS_RXD_62") (pintype "input"))
      (node (ref "U3") (pin "8") (pinfunction "IO32_8") (pintype "bidirectional"))
    )
    (net (code "36") (name "Net-(U2-GPS_TXD)") (class "Default")
      (node (ref "U2") (pin "61") (pinfunction "GPS_TXD_61") (pintype "output"))
      (node (ref "U3") (pin "9") (pinfunction "IO33_9") (pintype "bidirectional"))
    )
    (net (code "37") (name "Net-(U2-GSM_ANT)") (class "Default")
      (node (ref "C16") (pin "1") (pinfunction "1_1") (pintype "passive"))
      (node (ref "R17") (pin "2") (pinfunction "2_2") (pintype "passive"))
      (node (ref "U2") (pin "32") (pinfunction "GSM_ANT_32") (pintype "bidirectional"))
    )
    (net (code "38") (name "Net-(U2-SIM1_CLK)") (class "Default")
      (node (ref "R15") (pin "1") (pinfunction "1_1") (pintype "passive"))
      (node (ref "U2") (pin "16") (pinfunction "SIM1_CLK_16") (pintype "output"))
    )
    (net (code "39") (name "Net-(U2-SIM1_DATA)") (class "Default")
      (node (ref "R16") (pin "1") (pinfunction "1_1") (pintype "passive"))
      (node (ref "U2") (pin "15") (pinfunction "SIM1_DATA_15") (pintype "bidirectional"))
    )
    (net (code "40") (name "Net-(U2-SIM1_RST)") (class "Default")
      (node (ref "R14") (pin "1") (pinfunction "1_1") (pintype "passive"))
      (node (ref "U2") (pin "17") (pinfunction "SIM1_RST_17") (pintype "output"))
    )
    (net (code "41") (name "Net-(U2-UART1_RXD)") (class "Default")
      (node (ref "U2") (pin "2") (pinfunction "UART1_RXD_2") (pintype "input"))
      (node (ref "U3") (pin "28") (pinfunction "IO17_28") (pintype "bidirectional"))
    )
    (net (code "42") (name "Net-(U2-UART1_TXD)") (class "Default")
      (node (ref "U2") (pin "1") (pinfunction "UART1_TXD_1") (pintype "output"))
      (node (ref "U3") (pin "27") (pinfunction "IO16_27") (pintype "bidirectional"))
    )
    (net (code "43") (name "Net-(U2-VRTC)") (class "Default")
      (node (ref "U2") (pin "28") (pinfunction "VRTC_28") (pintype "power_in"))
      (node (ref "U3") (pin "7") (pinfunction "IO35_7") (pintype "input"))
    )
    (net (code "44") (name "Net-(U3-IO2)") (class "Default")
      (node (ref "JP4") (pin "3") (pinfunction "3_3") (pintype "passive"))
      (node (ref "U3") (pin "24") (pinfunction "IO2_24") (pintype "bidirectional"))
    )
    (net (code "45") (name "Net-(U3-IO4)") (class "Default")
      (node (ref "JP3") (pin "3") (pinfunction "3_3") (pintype "passive"))
      (node (ref "U3") (pin "26") (pinfunction "IO4_26") (pintype "bidirectional"))
    )
    (net (code "46") (name "Net-(U3-IO5)") (class "Default")
      (node (ref "U3") (pin "29") (pinfunction "IO5_29") (pintype "bidirectional"))
      (node (ref "U6") (pin "12") (pinfunction "SCK_12") (pintype "input"))
    )
    (net (code "47") (name "Net-(U3-IO13)") (class "Default")
      (node (ref "R19") (pin "1") (pinfunction "1_1") (pintype "passive"))
      (node (ref "U3") (pin "16") (pinfunction "IO13_16") (pintype "bidirectional"))
    )
    (net (code "48") (name "Net-(U3-IO14)") (class "Default")
      (node (ref "U3") (pin "13") (pinfunction "IO14_13") (pintype "bidirectional"))
      (node (ref "U6") (pin "4") (pinfunction "RESET_4") (pintype "input"))
    )
    (net (code "49") (name "Net-(U3-IO18)") (class "Default")
      (node (ref "U3") (pin "30") (pinfunction "IO18_30") (pintype "bidirectional"))
      (node (ref "U6") (pin "15") (pinfunction "NSS_15") (pintype "input"))
    )
    (net (code "50") (name "Net-(U3-IO19)") (class "Default")
      (node (ref "U3") (pin "31") (pinfunction "IO19_31") (pintype "bidirectional"))
      (node (ref "U6") (pin "13") (pinfunction "MISO_13") (pintype "output"))
    )
    (net (code "51") (name "Net-(U3-IO21)") (class "Default")
      (node (ref "JP8") (pin "3") (pinfunction "3_3") (pintype "passive"))
      (node (ref "U3") (pin "33") (pinfunction "IO21_33") (pintype "bidirectional"))
    )
    (net (code "52") (name "Net-(U3-IO22)") (class "Default")
      (node (ref "JP8") (pin "4") (pinfunction "4_4") (pintype "passive"))
      (node (ref "U3") (pin "36") (pinfunction "IO22_36") (pintype "bidirectional"))
    )
    (net (code "53") (name "Net-(U3-IO27)") (class "Default")
      (node (ref "U3") (pin "12") (pinfunction "IO27_12") (pintype "bidirectional"))
      (node (ref "U6") (pin "14") (pinfunction "MOSI_14") (pintype "input"))
    )
    (net (code "54") (name "Net-(U3-IO34)") (class "Default")
      (node (ref "U3") (pin "6") (pinfunction "IO34_6") (pintype "input"))
      (node (ref "U6") (pin "5") (pinfunction "DI00_5") (pintype "bidirectional"))
    )
    (net (code "55") (name "Net-(U3-SENSOR_VN)") (class "Default")
      (node (ref "JP5") (pin "3") (pinfunction "3_3") (pintype "passive"))
      (node (ref "U3") (pin "5") (pinfunction "SENSOR_VN_5") (pintype "input"))
    )
    (net (code "56") (name "Net-(U3-SENSOR_VP)") (class "Default")
      (node (ref "JP6") (pin "3") (pinfunction "3_3") (pintype "passive"))
      (node (ref "U3") (pin "4") (pinfunction "SENSOR_VP_4") (pintype "input"))
    )
    (net (code "57") (name "Net-(U4-EN)") (class "Default")
      (node (ref "R3") (pin "1") (pinfunction "1_1") (pintype "passive"))
      (node (ref "U4") (pin "3") (pinfunction "EN_3") (pintype "input"))
    )
    (net (code "58") (name "Net-(U4-VIN)") (class "Default")
      (node (ref "C3") (pin "1") (pinfunction "1_1") (pintype "passive"))
      (node (ref "D1") (pin "C") (pinfunction "C_C") (pintype "passive"))
      (node (ref "R3") (pin "2") (pinfunction "2_2") (pintype "passive"))
      (node (ref "U4") (pin "1") (pinfunction "VIN_1") (pintype "power_in"))
      (node (ref "U5") (pin "2") (pinfunction "S_2") (pintype "passive"))
    )
    (net (code "59") (name "Net-(U7-PROG)") (class "Default")
      (node (ref "RPROG") (pin "1") (pinfunction "1_1") (pintype "passive"))
      (node (ref "U7") (pin "5") (pinfunction "PROG_5") (pintype "input"))
    )
    (net (code "60") (name "Net-(U7-STAT)") (class "Default")
      (node (ref "D4") (pin "C") (pinfunction "C_C") (pintype "passive"))
      (node (ref "U7") (pin "1") (pinfunction "STAT_1") (pintype "output"))
    )
    (net (code "61") (name "Net-(U8-EN)") (class "Default")
      (node (ref "R13") (pin "1") (pinfunction "1_1") (pintype "passive"))
      (node (ref "U8") (pin "2") (pinfunction "EN_2") (pintype "bidirectional"))
    )
    (net (code "62") (name "Net-(U8-FB)") (class "Default")
      (node (ref "R10") (pin "2") (pinfunction "2_2") (pintype "passive"))
      (node (ref "R8") (pin "1") (pinfunction "1_1") (pintype "passive"))
      (node (ref "U8") (pin "5") (pinfunction "FB_5") (pintype "bidirectional"))
    )
    (net (code "63") (name "Net-(U8-OUT)") (class "Default")
      (node (ref "C11") (pin "1") (pinfunction "1_1") (pintype "passive"))
      (node (ref "C8") (pin "1") (pinfunction "1_1") (pintype "passive"))
      (node (ref "D2") (pin "C") (pinfunction "C_C") (pintype "passive"))
      (node (ref "D3") (pin "C") (pinfunction "C_C") (pintype "passive"))
      (node (ref "D5") (pin "A") (pinfunction "A_A") (pintype "passive"))
      (node (ref "JP3") (pin "1") (pinfunction "1_1") (pintype "passive"))
      (node (ref "JP4") (pin "1") (pinfunction "1_1") (pintype "passive"))
      (node (ref "JP5") (pin "1") (pinfunction "1_1") (pintype "passive"))
      (node (ref "JP6") (pin "1") (pinfunction "1_1") (pintype "passive"))
      (node (ref "JP8") (pin "1") (pinfunction "1_1") (pintype "passive"))
      (node (ref "R8") (pin "2") (pinfunction "2_2") (pintype "passive"))
      (node (ref "U8") (pin "7") (pinfunction "OUT_7") (pintype "bidirectional"))
    )
    (net (code "64") (name "Net-(U8-RSET)") (class "Default")
      (node (ref "R11") (pin "2") (pinfunction "2_2") (pintype "passive"))
      (node (ref "U8") (pin "6") (pinfunction "RSET_6") (pintype "bidirectional"))
    )
    (net (code "65") (name "unconnected-(J2-ID-Pad4)") (class "Default")
      (node (ref "J2") (pin "4") (pinfunction "ID_4") (pintype "bidirectional"))
    )
    (net (code "66") (name "unconnected-(JP1-Pad2)") (class "Default")
      (node (ref "JP1") (pin "2") (pinfunction "2_2") (pintype "passive"))
    )
    (net (code "67") (name "unconnected-(JP2-Pad2)") (class "Default")
      (node (ref "JP2") (pin "2") (pinfunction "2_2") (pintype "passive"))
    )
    (net (code "68") (name "unconnected-(JP7-Pad2)") (class "Default")
      (node (ref "JP7") (pin "2") (pinfunction "2_2") (pintype "passive"))
    )
    (net (code "69") (name "unconnected-(U1-GPIO.0-Pad14)") (class "Default")
      (node (ref "U1") (pin "14") (pinfunction "GPIO.0_14") (pintype "bidirectional"))
    )
    (net (code "70") (name "unconnected-(U1-GPIO.1-Pad13)") (class "Default")
      (node (ref "U1") (pin "13") (pinfunction "GPIO.1_13") (pintype "bidirectional"))
    )
    (net (code "71") (name "unconnected-(U1-GPIO.2-Pad12)") (class "Default")
      (node (ref "U1") (pin "12") (pinfunction "GPIO.2_12") (pintype "bidirectional"))
    )
    (net (code "72") (name "unconnected-(U1-GPIO.3-Pad11)") (class "Default")
      (node (ref "U1") (pin "11") (pinfunction "GPIO.3_11") (pintype "bidirectional"))
    )
    (net (code "73") (name "unconnected-(U1-SUSPEND-Pad17)") (class "Default")
      (node (ref "U1") (pin "17") (pinfunction "SUSPEND_17") (pintype "output"))
    )
    (net (code "74") (name "unconnected-(U1-VPP-Pad16)") (class "Default")
      (node (ref "U1") (pin "16") (pinfunction "VPP_16") (pintype "passive"))
    )
    (net (code "75") (name "unconnected-(U1-~{CTS}-Pad18)") (class "Default")
      (node (ref "U1") (pin "18") (pinfunction "~{CTS}_18") (pintype "input"))
    )
    (net (code "76") (name "unconnected-(U1-~{DCD}-Pad24)") (class "Default")
      (node (ref "U1") (pin "24") (pinfunction "~{DCD}_24") (pintype "input"))
    )
    (net (code "77") (name "unconnected-(U1-~{DSR}-Pad22)") (class "Default")
      (node (ref "U1") (pin "22") (pinfunction "~{DSR}_22") (pintype "input"))
    )
    (net (code "78") (name "unconnected-(U1-~{DTR}-Pad23)") (class "Default")
      (node (ref "U1") (pin "23") (pinfunction "~{DTR}_23") (pintype "output"))
    )
    (net (code "79") (name "unconnected-(U1-~{RI}-Pad1)") (class "Default")
      (node (ref "U1") (pin "1") (pinfunction "~{RI}_1") (pintype "input"))
    )
    (net (code "80") (name "unconnected-(U1-~{RST}-Pad9)") (class "Default")
      (node (ref "U1") (pin "9") (pinfunction "~{RST}_9") (pintype "bidirectional"))
    )
    (net (code "81") (name "unconnected-(U1-~{RTS}-Pad19)") (class "Default")
      (node (ref "U1") (pin "19") (pinfunction "~{RTS}_19") (pintype "output"))
    )
    (net (code "82") (name "unconnected-(U1-~{SUSPEND}-Pad15)") (class "Default")
      (node (ref "U1") (pin "15") (pinfunction "~{SUSPEND}_15") (pintype "output"))
    )
    (net (code "83") (name "unconnected-(U2-1PPS-Pad60)") (class "Default")
      (node (ref "U2") (pin "60") (pinfunction "1PPS_60") (pintype "output"))
    )
    (net (code "84") (name "unconnected-(U2-ADC-Pad38)") (class "Default")
      (node (ref "U2") (pin "38") (pinfunction "ADC_38") (pintype "input"))
    )
    (net (code "85") (name "unconnected-(U2-BT_ANT-Pad20)") (class "Default")
      (node (ref "U2") (pin "20") (pinfunction "BT_ANT_20") (pintype "bidirectional"))
    )
    (net (code "86") (name "unconnected-(U2-GNSS_EN-Pad59)") (class "Default")
      (node (ref "U2") (pin "59") (pinfunction "GNSS_EN_59") (pintype "input"))
    )
    (net (code "87") (name "unconnected-(U2-GPIO1-Pad57)") (class "Default")
      (node (ref "U2") (pin "57") (pinfunction "GPIO1_57") (pintype "bidirectional"))
    )
    (net (code "88") (name "unconnected-(U2-GPIO2-Pad58)") (class "Default")
      (node (ref "U2") (pin "58") (pinfunction "GPIO2_58") (pintype "bidirectional"))
    )
    (net (code "89") (name "unconnected-(U2-MCCA0-Pad49)") (class "Default")
      (node (ref "U2") (pin "49") (pinfunction "MCCA0_49") (pintype "bidirectional"))
    )
    (net (code "90") (name "unconnected-(U2-MCCA1-Pad48)") (class "Default")
      (node (ref "U2") (pin "48") (pinfunction "MCCA1_48") (pintype "bidirectional"))
    )
    (net (code "91") (name "unconnected-(U2-MCCA2-Pad47)") (class "Default")
      (node (ref "U2") (pin "47") (pinfunction "MCCA2_47") (pintype "bidirectional"))
    )
    (net (code "92") (name "unconnected-(U2-MCCA3-Pad46)") (class "Default")
      (node (ref "U2") (pin "46") (pinfunction "MCCA3_46") (pintype "bidirectional"))
    )
    (net (code "93") (name "unconnected-(U2-MCCK-Pad50)") (class "Default")
      (node (ref "U2") (pin "50") (pinfunction "MCCK_50") (pintype "bidirectional"))
    )
    (net (code "94") (name "unconnected-(U2-MCCM0-Pad51)") (class "Default")
      (node (ref "U2") (pin "51") (pinfunction "MCCM0_51") (pintype "bidirectional"))
    )
    (net (code "95") (name "unconnected-(U2-MICN-Pad10)") (class "Default")
      (node (ref "U2") (pin "10") (pinfunction "MICN_10") (pintype "input"))
    )
    (net (code "96") (name "unconnected-(U2-MICP-Pad9)") (class "Default")
      (node (ref "U2") (pin "9") (pinfunction "MICP_9") (pintype "input"))
    )
    (net (code "97") (name "unconnected-(U2-NETLIGHT-Pad41)") (class "Default")
      (node (ref "U2") (pin "41") (pinfunction "NETLIGHT_41") (pintype "output"))
    )
    (net (code "98") (name "unconnected-(U2-PWRKEY-Pad39)") (class "Default")
      (node (ref "U2") (pin "39") (pinfunction "PWRKEY_39") (pintype "input"))
    )
    (net (code "99") (name "unconnected-(U2-RF_SYNC-Pad29)") (class "Default")
      (node (ref "U2") (pin "29") (pinfunction "RF_SYNC_29") (pintype "output"))
    )
    (net (code "100") (name "unconnected-(U2-SCL-Pad65)") (class "Default")
      (node (ref "U2") (pin "65") (pinfunction "SCL_65") (pintype "output"))
    )
    (net (code "101") (name "unconnected-(U2-SDA-Pad64)") (class "Default")
      (node (ref "U2") (pin "64") (pinfunction "SDA_64") (pintype "bidirectional"))
    )
    (net (code "102") (name "unconnected-(U2-SIM1_DET-Pad14)") (class "Default")
      (node (ref "U2") (pin "14") (pinfunction "SIM1_DET_14") (pintype "input"))
    )
    (net (code "103") (name "unconnected-(U2-SIM2_CLK-Pad54)") (class "Default")
      (node (ref "U2") (pin "54") (pinfunction "SIM2_CLK_54") (pintype "output"))
    )
    (net (code "104") (name "unconnected-(U2-SIM2_DATA-Pad53)") (class "Default")
      (node (ref "U2") (pin "53") (pinfunction "SIM2_DATA_53") (pintype "bidirectional"))
    )
    (net (code "105") (name "unconnected-(U2-SIM2_DET-Pad52)") (class "Default")
      (node (ref "U2") (pin "52") (pinfunction "SIM2_DET_52") (pintype "input"))
    )
    (net (code "106") (name "unconnected-(U2-SIM2_RST-Pad55)") (class "Default")
      (node (ref "U2") (pin "55") (pinfunction "SIM2_RST_55") (pintype "output"))
    )
    (net (code "107") (name "unconnected-(U2-SIM2_VDD-Pad56)") (class "Default")
      (node (ref "U2") (pin "56") (pinfunction "SIM2_VDD_56") (pintype "output"))
    )
    (net (code "108") (name "unconnected-(U2-SPK1N-Pad12)") (class "Default")
      (node (ref "U2") (pin "12") (pinfunction "SPK1N_12") (pintype "output"))
    )
    (net (code "109") (name "unconnected-(U2-SPK1P-Pad11)") (class "Default")
      (node (ref "U2") (pin "11") (pinfunction "SPK1P_11") (pintype "output"))
    )
    (net (code "110") (name "unconnected-(U2-SPK2N-Pad43)") (class "Default")
      (node (ref "U2") (pin "43") (pinfunction "SPK2N_43") (pintype "output"))
    )
    (net (code "111") (name "unconnected-(U2-SPK2P-Pad44)") (class "Default")
      (node (ref "U2") (pin "44") (pinfunction "SPK2P_44") (pintype "output"))
    )
    (net (code "112") (name "unconnected-(U2-STATUS-Pad42)") (class "Default")
      (node (ref "U2") (pin "42") (pinfunction "STATUS_42") (pintype "output"))
    )
    (net (code "113") (name "unconnected-(U2-UART1_CTS-Pad4)") (class "Default")
      (node (ref "U2") (pin "4") (pinfunction "UART1_CTS_4") (pintype "output"))
    )
    (net (code "114") (name "unconnected-(U2-UART1_DCD-Pad5)") (class "Default")
      (node (ref "U2") (pin "5") (pinfunction "UART1_DCD_5") (pintype "output"))
    )
    (net (code "115") (name "unconnected-(U2-UART1_DTR-Pad6)") (class "Default")
      (node (ref "U2") (pin "6") (pinfunction "UART1_DTR_6") (pintype "input"))
    )
    (net (code "116") (name "unconnected-(U2-UART1_RI-Pad7)") (class "Default")
      (node (ref "U2") (pin "7") (pinfunction "UART1_RI_7") (pintype "output"))
    )
    (net (code "117") (name "unconnected-(U2-UART1_RTS-Pad3)") (class "Default")
      (node (ref "U2") (pin "3") (pinfunction "UART1_RTS_3") (pintype "input"))
    )
    (net (code "118") (name "unconnected-(U2-UART2_RXD-Pad23)") (class "Default")
      (node (ref "U2") (pin "23") (pinfunction "UART2_RXD_23") (pintype "input"))
    )
    (net (code "119") (name "unconnected-(U2-UART2_TXD-Pad22)") (class "Default")
      (node (ref "U2") (pin "22") (pinfunction "UART2_TXD_22") (pintype "output"))
    )
    (net (code "120") (name "unconnected-(U2-USB_DM-Pad26)") (class "Default")
      (node (ref "U2") (pin "26") (pinfunction "USB_DM_26") (pintype "bidirectional"))
    )
    (net (code "121") (name "unconnected-(U2-USB_DP-Pad25)") (class "Default")
      (node (ref "U2") (pin "25") (pinfunction "USB_DP_25") (pintype "bidirectional"))
    )
    (net (code "122") (name "unconnected-(U2-USB_VBUS-Pad24)") (class "Default")
      (node (ref "U2") (pin "24") (pinfunction "USB_VBUS_24") (pintype "input"))
    )
    (net (code "123") (name "unconnected-(U2-VDD_EXT-Pad40)") (class "Default")
      (node (ref "U2") (pin "40") (pinfunction "VDD_EXT_40") (pintype "output"))
    )
    (net (code "124") (name "unconnected-(U3-IO0-Pad25)") (class "Default")
      (node (ref "U3") (pin "25") (pinfunction "IO0_25") (pintype "bidirectional"))
    )
    (net (code "125") (name "unconnected-(U3-IO12-Pad14)") (class "Default")
      (node (ref "U3") (pin "14") (pinfunction "IO12_14") (pintype "bidirectional"))
    )
    (net (code "126") (name "unconnected-(U3-IO15-Pad23)") (class "Default")
      (node (ref "U3") (pin "23") (pinfunction "IO15_23") (pintype "bidirectional"))
    )
    (net (code "127") (name "unconnected-(U3-IO23-Pad37)") (class "Default")
      (node (ref "U3") (pin "37") (pinfunction "IO23_37") (pintype "bidirectional"))
    )
    (net (code "128") (name "unconnected-(U3-SCK{slash}CLK-Pad20)") (class "Default")
      (node (ref "U3") (pin "20") (pinfunction "SCK/CLK_20") (pintype "bidirectional"))
    )
    (net (code "129") (name "unconnected-(U3-SCS{slash}CMD-Pad19)") (class "Default")
      (node (ref "U3") (pin "19") (pinfunction "SCS/CMD_19") (pintype "bidirectional"))
    )
    (net (code "130") (name "unconnected-(U3-SDI{slash}SD1-Pad22)") (class "Default")
      (node (ref "U3") (pin "22") (pinfunction "SDI/SD1_22") (pintype "bidirectional"))
    )
    (net (code "131") (name "unconnected-(U3-SDO{slash}SD0-Pad21)") (class "Default")
      (node (ref "U3") (pin "21") (pinfunction "SDO/SD0_21") (pintype "bidirectional"))
    )
    (net (code "132") (name "unconnected-(U3-SHD{slash}SD2-Pad17)") (class "Default")
      (node (ref "U3") (pin "17") (pinfunction "SHD/SD2_17") (pintype "bidirectional"))
    )
    (net (code "133") (name "unconnected-(U3-SWP{slash}SD3-Pad18)") (class "Default")
      (node (ref "U3") (pin "18") (pinfunction "SWP/SD3_18") (pintype "bidirectional"))
    )
    (net (code "134") (name "unconnected-(U6-DI01-Pad6)") (class "Default")
      (node (ref "U6") (pin "6") (pinfunction "DI01_6") (pintype "bidirectional"))
    )
    (net (code "135") (name "unconnected-(U6-DI02-Pad7)") (class "Default")
      (node (ref "U6") (pin "7") (pinfunction "DI02_7") (pintype "bidirectional"))
    )
    (net (code "136") (name "unconnected-(U6-DI03-Pad8)") (class "Default")
      (node (ref "U6") (pin "8") (pinfunction "DI03_8") (pintype "bidirectional"))
    )
    (net (code "137") (name "unconnected-(U6-DI04-Pad10)") (class "Default")
      (node (ref "U6") (pin "10") (pinfunction "DI04_10") (pintype "bidirectional"))
    )
    (net (code "138") (name "unconnected-(U6-DI05-Pad11)") (class "Default")
      (node (ref "U6") (pin "11") (pinfunction "DI05_11") (pintype "bidirectional"))
    )
  )
)
